# SparkFun_SSOP16_Breakout.net
KiCad netlist of a schematic drawn in EAGLE
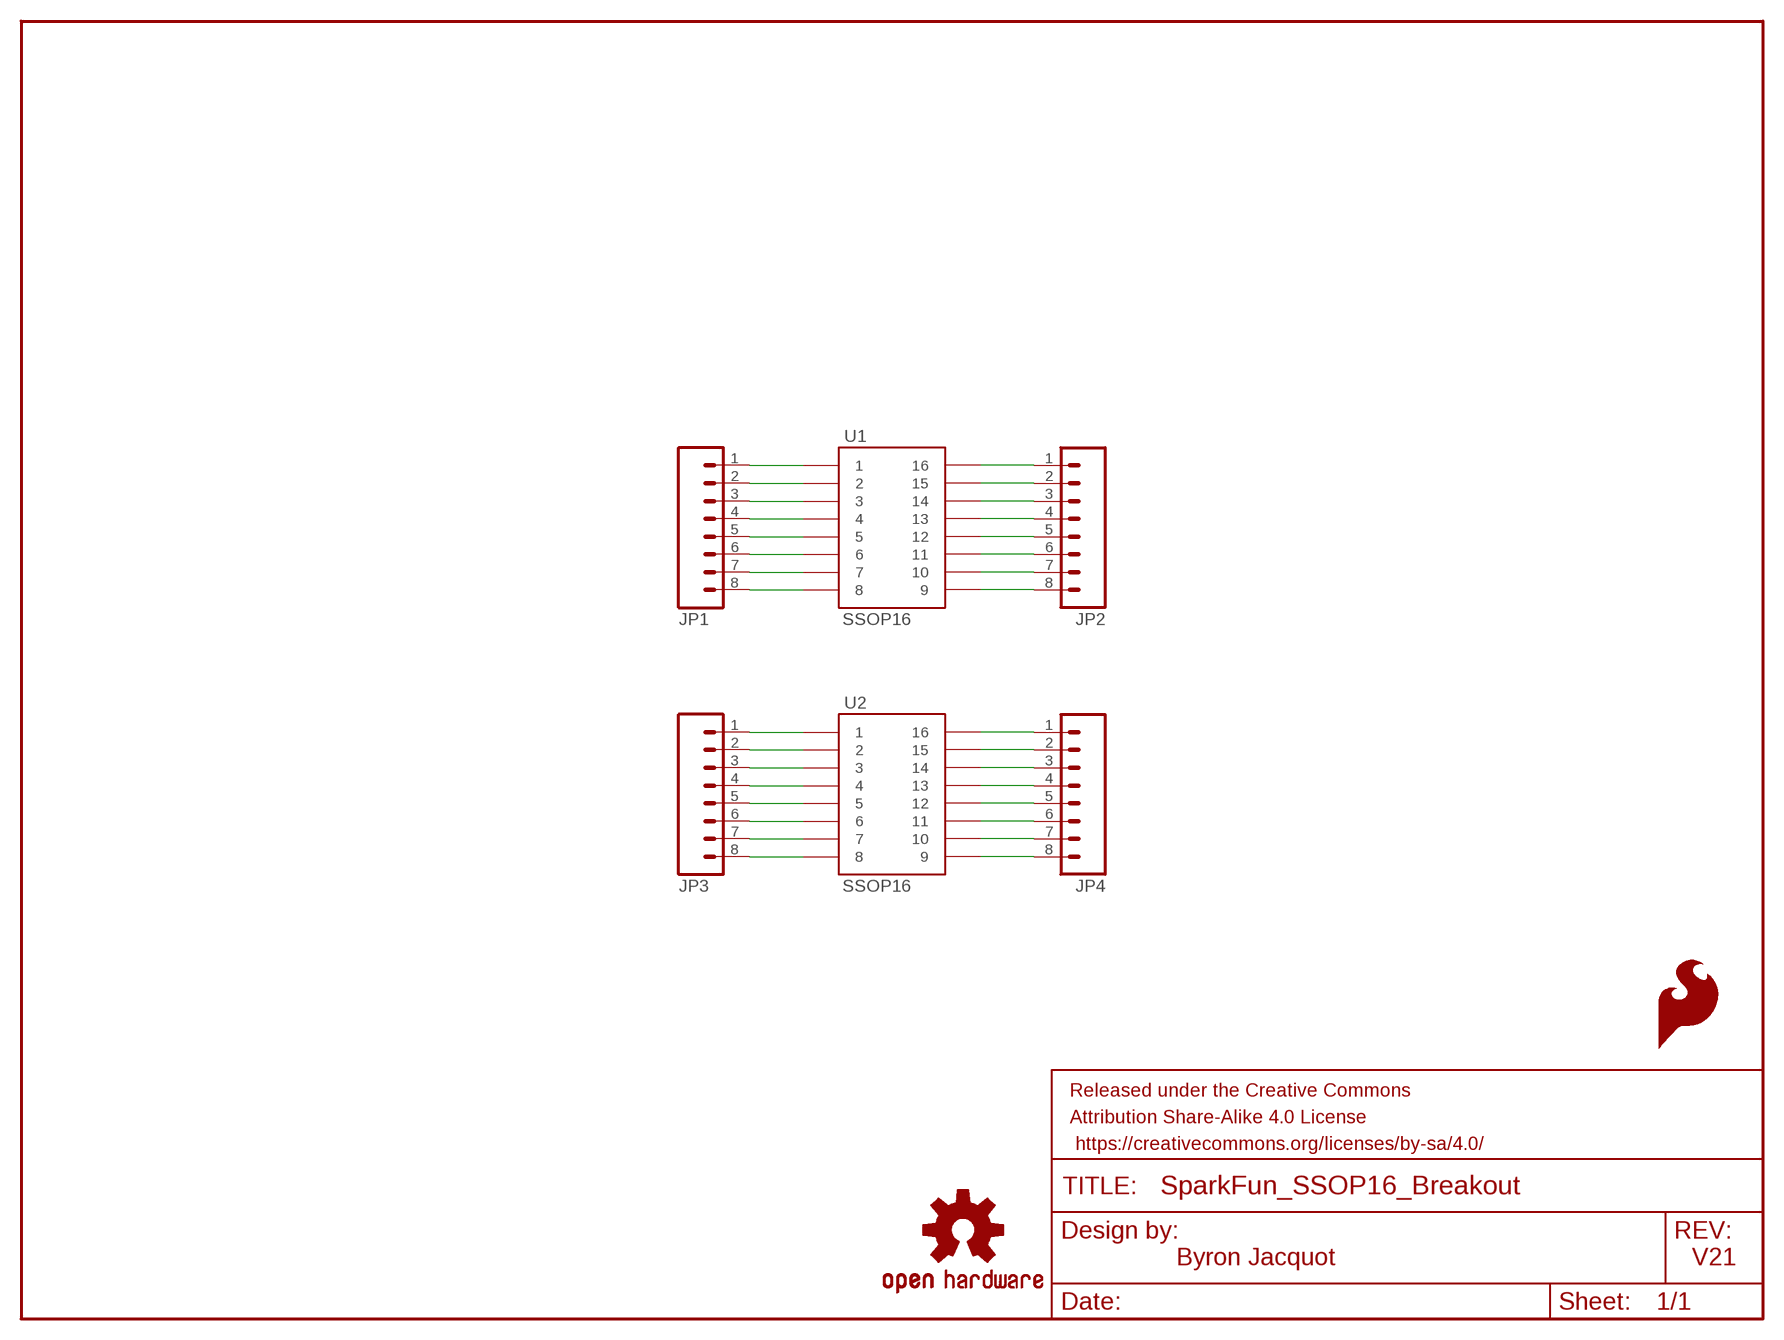
[diagram p0: schematic, sheet 1]

(export (version "E")
  (design (tool "Eeschema 10.0.6"))
  (components
    (comp (ref "FRAME1")
      (value "FRAME-LETTER")
      (footprint "eagle-import:CREATIVE_COMMONS")
      (libsource (lib "eagle-import") (part "FRAME-LETTER"))
    )
    (comp (ref "JP1")
      (value "M08NO_SILK")
      (footprint "eagle-import:1X08_PIN1_NO_SILK")
      (libsource (lib "eagle-import") (part "M08NO_SILK"))
    )
    (comp (ref "JP2")
      (value "M08NO_SILK_FEMALE_PTH")
      (footprint "eagle-import:1X08_NO_SILK")
      (libsource (lib "eagle-import") (part "M08NO_SILK_FEMALE_PTH"))
    )
    (comp (ref "JP3")
      (value "M08NO_SILK")
      (footprint "eagle-import:1X08_PIN1_NO_SILK")
      (libsource (lib "eagle-import") (part "M08NO_SILK"))
    )
    (comp (ref "JP4")
      (value "M08NO_SILK_FEMALE_PTH")
      (footprint "eagle-import:1X08_NO_SILK")
      (libsource (lib "eagle-import") (part "M08NO_SILK_FEMALE_PTH"))
    )
    (comp (ref "LOGO1")
      (value "SFE_LOGO_FLAME.1_INCH")
      (footprint "eagle-import:SFE_LOGO_FLAME_.1")
      (libsource (lib "eagle-import") (part "SFE_LOGO_FLAME.1_INCH"))
    )
    (comp (ref "LOGO2")
      (value "SFE_LOGO_FLAME.1_INCH")
      (footprint "eagle-import:SFE_LOGO_FLAME_.1")
      (libsource (lib "eagle-import") (part "SFE_LOGO_FLAME.1_INCH"))
    )
    (comp (ref "LOGO3")
      (value "OSHW-LOGOS")
      (footprint "eagle-import:OSHW-LOGO-S")
      (libsource (lib "eagle-import") (part "OSHW-LOGOS"))
    )
    (comp (ref "LOGO4")
      (value "OSHW-LOGOS")
      (footprint "eagle-import:OSHW-LOGO-S")
      (libsource (lib "eagle-import") (part "OSHW-LOGOS"))
    )
    (comp (ref "U1")
      (value "SSOP16")
      (footprint "eagle-import:SSOP16")
      (libsource (lib "eagle-import") (part "SSOP16"))
    )
    (comp (ref "U2")
      (value "SSOP16")
      (footprint "eagle-import:SSOP16")
      (libsource (lib "eagle-import") (part "SSOP16"))
    )
  )
  (nets
    (net (code "1") (name "Net-(U1-1)") (class "Default")
      (node (ref "JP1") (pin "1") (pinfunction "1_1") (pintype "passive"))
      (node (ref "U1") (pin "P$1") (pinfunction "1_P$1") (pintype "bidirectional"))
    )
    (net (code "2") (name "Net-(U1-2)") (class "Default")
      (node (ref "JP1") (pin "2") (pinfunction "2_2") (pintype "passive"))
      (node (ref "U1") (pin "P$2") (pinfunction "2_P$2") (pintype "bidirectional"))
    )
    (net (code "3") (name "Net-(U1-3)") (class "Default")
      (node (ref "JP1") (pin "3") (pinfunction "3_3") (pintype "passive"))
      (node (ref "U1") (pin "P$3") (pinfunction "3_P$3") (pintype "bidirectional"))
    )
    (net (code "4") (name "Net-(U1-4)") (class "Default")
      (node (ref "JP1") (pin "4") (pinfunction "4_4") (pintype "passive"))
      (node (ref "U1") (pin "P$4") (pinfunction "4_P$4") (pintype "bidirectional"))
    )
    (net (code "5") (name "Net-(U1-5)") (class "Default")
      (node (ref "JP1") (pin "5") (pinfunction "5_5") (pintype "passive"))
      (node (ref "U1") (pin "P$5") (pinfunction "5_P$5") (pintype "bidirectional"))
    )
    (net (code "6") (name "Net-(U1-6)") (class "Default")
      (node (ref "JP1") (pin "6") (pinfunction "6_6") (pintype "passive"))
      (node (ref "U1") (pin "P$6") (pinfunction "6_P$6") (pintype "bidirectional"))
    )
    (net (code "7") (name "Net-(U1-7)") (class "Default")
      (node (ref "JP1") (pin "7") (pinfunction "7_7") (pintype "passive"))
      (node (ref "U1") (pin "P$7") (pinfunction "7_P$7") (pintype "bidirectional"))
    )
    (net (code "8") (name "Net-(U1-8)") (class "Default")
      (node (ref "JP1") (pin "8") (pinfunction "8_8") (pintype "passive"))
      (node (ref "U1") (pin "P$8") (pinfunction "8_P$8") (pintype "bidirectional"))
    )
    (net (code "9") (name "Net-(U1-9)") (class "Default")
      (node (ref "JP2") (pin "8") (pinfunction "8_8") (pintype "passive"))
      (node (ref "U1") (pin "P$9") (pinfunction "9_P$9") (pintype "bidirectional"))
    )
    (net (code "10") (name "Net-(U1-10)") (class "Default")
      (node (ref "JP2") (pin "7") (pinfunction "7_7") (pintype "passive"))
      (node (ref "U1") (pin "P$10") (pinfunction "10_P$10") (pintype "bidirectional"))
    )
    (net (code "11") (name "Net-(U1-11)") (class "Default")
      (node (ref "JP2") (pin "6") (pinfunction "6_6") (pintype "passive"))
      (node (ref "U1") (pin "P$11") (pinfunction "11_P$11") (pintype "bidirectional"))
    )
    (net (code "12") (name "Net-(U1-12)") (class "Default")
      (node (ref "JP2") (pin "5") (pinfunction "5_5") (pintype "passive"))
      (node (ref "U1") (pin "P$12") (pinfunction "12_P$12") (pintype "bidirectional"))
    )
    (net (code "13") (name "Net-(U1-13)") (class "Default")
      (node (ref "JP2") (pin "4") (pinfunction "4_4") (pintype "passive"))
      (node (ref "U1") (pin "P$13") (pinfunction "13_P$13") (pintype "bidirectional"))
    )
    (net (code "14") (name "Net-(U1-14)") (class "Default")
      (node (ref "JP2") (pin "3") (pinfunction "3_3") (pintype "passive"))
      (node (ref "U1") (pin "P$14") (pinfunction "14_P$14") (pintype "bidirectional"))
    )
    (net (code "15") (name "Net-(U1-15)") (class "Default")
      (node (ref "JP2") (pin "2") (pinfunction "2_2") (pintype "passive"))
      (node (ref "U1") (pin "P$15") (pinfunction "15_P$15") (pintype "bidirectional"))
    )
    (net (code "16") (name "Net-(U1-16)") (class "Default")
      (node (ref "JP2") (pin "1") (pinfunction "1_1") (pintype "passive"))
      (node (ref "U1") (pin "P$16") (pinfunction "16_P$16") (pintype "bidirectional"))
    )
    (net (code "17") (name "Net-(U2-1)") (class "Default")
      (node (ref "JP3") (pin "1") (pinfunction "1_1") (pintype "passive"))
      (node (ref "U2") (pin "P$1") (pinfunction "1_P$1") (pintype "bidirectional"))
    )
    (net (code "18") (name "Net-(U2-2)") (class "Default")
      (node (ref "JP3") (pin "2") (pinfunction "2_2") (pintype "passive"))
      (node (ref "U2") (pin "P$2") (pinfunction "2_P$2") (pintype "bidirectional"))
    )
    (net (code "19") (name "Net-(U2-3)") (class "Default")
      (node (ref "JP3") (pin "3") (pinfunction "3_3") (pintype "passive"))
      (node (ref "U2") (pin "P$3") (pinfunction "3_P$3") (pintype "bidirectional"))
    )
    (net (code "20") (name "Net-(U2-4)") (class "Default")
      (node (ref "JP3") (pin "4") (pinfunction "4_4") (pintype "passive"))
      (node (ref "U2") (pin "P$4") (pinfunction "4_P$4") (pintype "bidirectional"))
    )
    (net (code "21") (name "Net-(U2-5)") (class "Default")
      (node (ref "JP3") (pin "5") (pinfunction "5_5") (pintype "passive"))
      (node (ref "U2") (pin "P$5") (pinfunction "5_P$5") (pintype "bidirectional"))
    )
    (net (code "22") (name "Net-(U2-6)") (class "Default")
      (node (ref "JP3") (pin "6") (pinfunction "6_6") (pintype "passive"))
      (node (ref "U2") (pin "P$6") (pinfunction "6_P$6") (pintype "bidirectional"))
    )
    (net (code "23") (name "Net-(U2-7)") (class "Default")
      (node (ref "JP3") (pin "7") (pinfunction "7_7") (pintype "passive"))
      (node (ref "U2") (pin "P$7") (pinfunction "7_P$7") (pintype "bidirectional"))
    )
    (net (code "24") (name "Net-(U2-8)") (class "Default")
      (node (ref "JP3") (pin "8") (pinfunction "8_8") (pintype "passive"))
      (node (ref "U2") (pin "P$8") (pinfunction "8_P$8") (pintype "bidirectional"))
    )
    (net (code "25") (name "Net-(U2-9)") (class "Default")
      (node (ref "JP4") (pin "8") (pinfunction "8_8") (pintype "passive"))
      (node (ref "U2") (pin "P$9") (pinfunction "9_P$9") (pintype "bidirectional"))
    )
    (net (code "26") (name "Net-(U2-10)") (class "Default")
      (node (ref "JP4") (pin "7") (pinfunction "7_7") (pintype "passive"))
      (node (ref "U2") (pin "P$10") (pinfunction "10_P$10") (pintype "bidirectional"))
    )
    (net (code "27") (name "Net-(U2-11)") (class "Default")
      (node (ref "JP4") (pin "6") (pinfunction "6_6") (pintype "passive"))
      (node (ref "U2") (pin "P$11") (pinfunction "11_P$11") (pintype "bidirectional"))
    )
    (net (code "28") (name "Net-(U2-12)") (class "Default")
      (node (ref "JP4") (pin "5") (pinfunction "5_5") (pintype "passive"))
      (node (ref "U2") (pin "P$12") (pinfunction "12_P$12") (pintype "bidirectional"))
    )
    (net (code "29") (name "Net-(U2-13)") (class "Default")
      (node (ref "JP4") (pin "4") (pinfunction "4_4") (pintype "passive"))
      (node (ref "U2") (pin "P$13") (pinfunction "13_P$13") (pintype "bidirectional"))
    )
    (net (code "30") (name "Net-(U2-14)") (class "Default")
      (node (ref "JP4") (pin "3") (pinfunction "3_3") (pintype "passive"))
      (node (ref "U2") (pin "P$14") (pinfunction "14_P$14") (pintype "bidirectional"))
    )
    (net (code "31") (name "Net-(U2-15)") (class "Default")
      (node (ref "JP4") (pin "2") (pinfunction "2_2") (pintype "passive"))
      (node (ref "U2") (pin "P$15") (pinfunction "15_P$15") (pintype "bidirectional"))
    )
    (net (code "32") (name "Net-(U2-16)") (class "Default")
      (node (ref "JP4") (pin "1") (pinfunction "1_1") (pintype "passive"))
      (node (ref "U2") (pin "P$16") (pinfunction "16_P$16") (pintype "bidirectional"))
    )
  )
)
